# USB_MiniPower.net
KiCad netlist of a schematic drawn in EAGLE
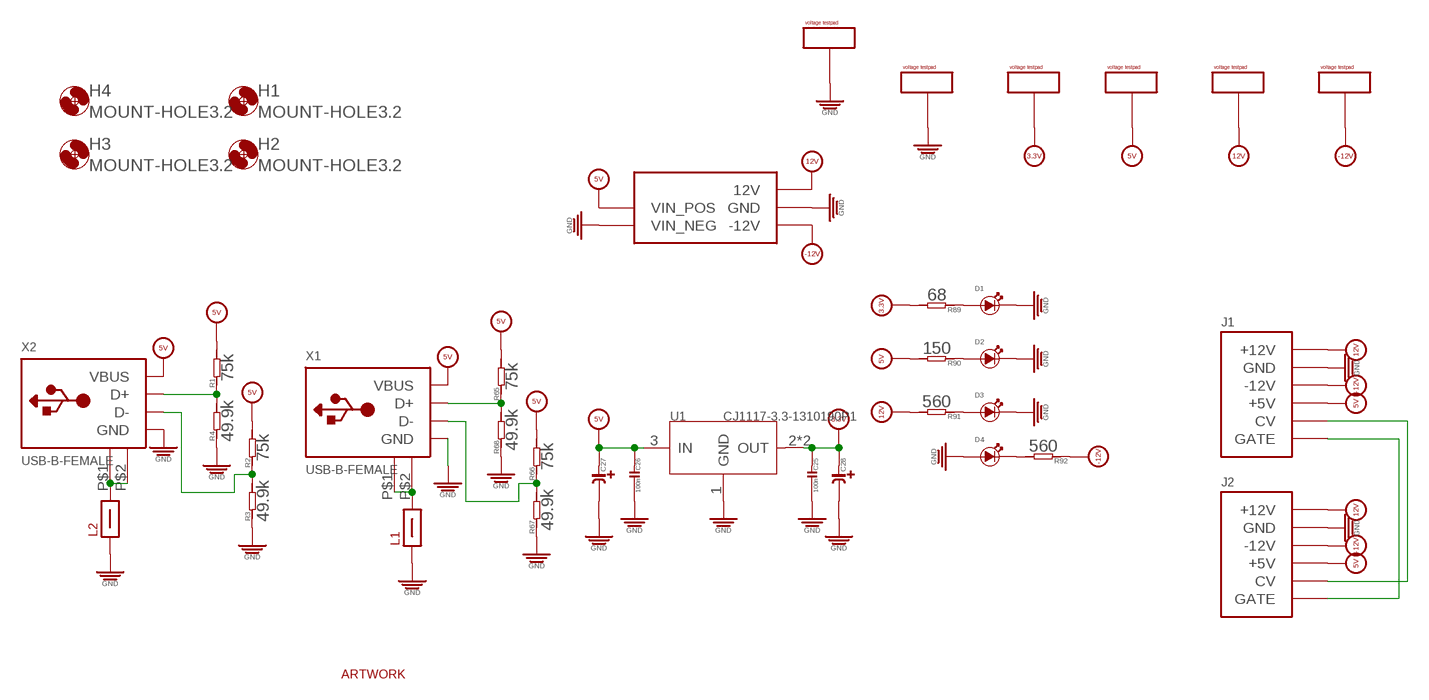
[diagram p0: schematic, sheet 1]

(export (version "E")
  (design (tool "Eeschema 10.0.6"))
  (components
    (comp (ref "C25")
      (value "100n")
      (footprint "eagle-import:C0603")
      (libsource (lib "eagle-import") (part "C-0603"))
    )
    (comp (ref "C26")
      (value "100n")
      (footprint "eagle-import:C0603")
      (libsource (lib "eagle-import") (part "C-0603"))
    )
    (comp (ref "C27")
      (value "C-POLAR-A")
      (footprint "eagle-import:CASE-A_3216")
      (libsource (lib "eagle-import") (part "C-POLAR-A"))
    )
    (comp (ref "C28")
      (value "C-POLAR-A")
      (footprint "eagle-import:CASE-A_3216")
      (libsource (lib "eagle-import") (part "C-POLAR-A"))
    )
    (comp (ref "D1")
      (value "LED")
      (footprint "eagle-import:LED0603")
      (libsource (lib "eagle-import") (part "LED"))
    )
    (comp (ref "D2")
      (value "LED")
      (footprint "eagle-import:LED0603")
      (libsource (lib "eagle-import") (part "LED"))
    )
    (comp (ref "D3")
      (value "LED")
      (footprint "eagle-import:LED0603")
      (libsource (lib "eagle-import") (part "LED"))
    )
    (comp (ref "D4")
      (value "LED")
      (footprint "eagle-import:LED0603")
      (libsource (lib "eagle-import") (part "LED"))
    )
    (comp (ref "H1")
      (value "MOUNT-HOLE3.2")
      (footprint "eagle-import:3,2")
      (libsource (lib "eagle-import") (part "MOUNT-HOLE3.2"))
    )
    (comp (ref "H2")
      (value "MOUNT-HOLE3.2")
      (footprint "eagle-import:3,2")
      (libsource (lib "eagle-import") (part "MOUNT-HOLE3.2"))
    )
    (comp (ref "H3")
      (value "MOUNT-HOLE3.2")
      (footprint "eagle-import:3,2")
      (libsource (lib "eagle-import") (part "MOUNT-HOLE3.2"))
    )
    (comp (ref "H4")
      (value "MOUNT-HOLE3.2")
      (footprint "eagle-import:3,2")
      (libsource (lib "eagle-import") (part "MOUNT-HOLE3.2"))
    )
    (comp (ref "J1")
      (value "POWER_SHROUDED_NOTEXT")
      (footprint "eagle-import:POWER_16_SHROUDED_NOTEXT")
      (libsource (lib "eagle-import") (part "POWER_SHROUDED_NOTEXT"))
    )
    (comp (ref "J2")
      (value "POWERSHROUDED")
      (footprint "eagle-import:POWER_16_SHROUDED")
      (libsource (lib "eagle-import") (part "POWERSHROUDED"))
    )
    (comp (ref "L1")
      (value "FERRITE_1812")
      (footprint "eagle-import:FERRITE_1812")
      (libsource (lib "eagle-import") (part "FERRITE_1812"))
    )
    (comp (ref "L2")
      (value "FERRITE_1812")
      (footprint "eagle-import:FERRITE_1812")
      (libsource (lib "eagle-import") (part "FERRITE_1812"))
    )
    (comp (ref "R1")
      (value "75k")
      (footprint "eagle-import:R0603")
      (libsource (lib "eagle-import") (part "R-0603"))
    )
    (comp (ref "R2")
      (value "75k")
      (footprint "eagle-import:R0603")
      (libsource (lib "eagle-import") (part "R-0603"))
    )
    (comp (ref "R3")
      (value "49.9k")
      (footprint "eagle-import:R0603")
      (libsource (lib "eagle-import") (part "R-0603"))
    )
    (comp (ref "R4")
      (value "49.9k")
      (footprint "eagle-import:R0603")
      (libsource (lib "eagle-import") (part "R-0603"))
    )
    (comp (ref "R65")
      (value "75k")
      (footprint "eagle-import:R0603")
      (libsource (lib "eagle-import") (part "R-0603"))
    )
    (comp (ref "R66")
      (value "75k")
      (footprint "eagle-import:R0603")
      (libsource (lib "eagle-import") (part "R-0603"))
    )
    (comp (ref "R67")
      (value "49.9k")
      (footprint "eagle-import:R0603")
      (libsource (lib "eagle-import") (part "R-0603"))
    )
    (comp (ref "R68")
      (value "49.9k")
      (footprint "eagle-import:R0603")
      (libsource (lib "eagle-import") (part "R-0603"))
    )
    (comp (ref "R89")
      (value "68")
      (footprint "eagle-import:R0603")
      (libsource (lib "eagle-import") (part "R-0603"))
    )
    (comp (ref "R90")
      (value "150")
      (footprint "eagle-import:R0603")
      (libsource (lib "eagle-import") (part "R-0603"))
    )
    (comp (ref "R91")
      (value "560")
      (footprint "eagle-import:R0603")
      (libsource (lib "eagle-import") (part "R-0603"))
    )
    (comp (ref "R92")
      (value "560")
      (footprint "eagle-import:R0603")
      (libsource (lib "eagle-import") (part "R-0603"))
    )
    (comp (ref "U$7")
      (value "VOLTAGETESTPAD_BIG")
      (footprint "eagle-import:POWERTESTPAD_BIG")
      (fields (field (name "DESC") "3.3V"))
      (libsource (lib "eagle-import") (part "VOLTAGETESTPAD_BIG"))
    )
    (comp (ref "U$8")
      (value "VOLTAGETESTPAD_BIG")
      (footprint "eagle-import:POWERTESTPAD_BIG")
      (fields (field (name "DESC") "5V"))
      (libsource (lib "eagle-import") (part "VOLTAGETESTPAD_BIG"))
    )
    (comp (ref "U$9")
      (value "VOLTAGETESTPAD_BIG")
      (footprint "eagle-import:POWERTESTPAD_BIG")
      (fields (field (name "DESC") "12V"))
      (libsource (lib "eagle-import") (part "VOLTAGETESTPAD_BIG"))
    )
    (comp (ref "U$10")
      (value "VOLTAGETESTPAD_BIG")
      (footprint "eagle-import:POWERTESTPAD_BIG")
      (fields (field (name "DESC") "-12V"))
      (libsource (lib "eagle-import") (part "VOLTAGETESTPAD_BIG"))
    )
    (comp (ref "U$11")
      (value "VOLTAGETESTPAD_BIG")
      (footprint "eagle-import:POWERTESTPAD_BIG")
      (fields (field (name "DESC") "GND"))
      (libsource (lib "eagle-import") (part "VOLTAGETESTPAD_BIG"))
    )
    (comp (ref "U$16")
      (value "VOLTAGETESTPAD_BIG")
      (footprint "eagle-import:POWERTESTPAD_BIG")
      (fields (field (name "DESC") "GND"))
      (libsource (lib "eagle-import") (part "VOLTAGETESTPAD_BIG"))
    )
    (comp (ref "U$17")
      (value "TINRS_ARTWORKTINYDATE")
      (footprint "eagle-import:JUSTATINYROCKET_DATECODE")
      (libsource (lib "eagle-import") (part "TINRS_ARTWORKTINYDATE"))
    )
    (comp (ref "U$42")
      (value "CINCONBRICK_12V")
      (footprint "eagle-import:CINCONBRICK")
      (libsource (lib "eagle-import") (part "CINCONBRICK_12V"))
    )
    (comp (ref "U1")
      (value "CJ1117-3.3-1310190P1")
      (footprint "eagle-import:SOT223")
      (libsource (lib "eagle-import") (part "CJ1117-3.3-1310190P1"))
    )
    (comp (ref "X1")
      (value "USB-B-FEMALE")
      (footprint "eagle-import:FCI61729")
      (libsource (lib "eagle-import") (part "USB-B-FEMALE"))
    )
    (comp (ref "X2")
      (value "USB-B-FEMALE")
      (footprint "eagle-import:FCI61729")
      (libsource (lib "eagle-import") (part "USB-B-FEMALE"))
    )
  )
  (nets
    (net (code "1") (name "-12V") (class "Default")
      (node (ref "J1") (pin "1") (pinfunction "-12V_1") (pintype "bidirectional"))
      (node (ref "J1") (pin "2") (pinfunction "-12V_2") (pintype "bidirectional"))
      (node (ref "J2") (pin "1") (pinfunction "-12V_1") (pintype "bidirectional"))
      (node (ref "J2") (pin "2") (pinfunction "-12V_2") (pintype "bidirectional"))
      (node (ref "R92") (pin "1") (pinfunction "1_1") (pintype "bidirectional"))
      (node (ref "U$10") (pin "P$1") (pinfunction "VOLTAGE_P$1") (pintype "bidirectional"))
      (node (ref "U$10") (pin "P$2") (pinfunction "VOLTAGE_P$2") (pintype "bidirectional"))
      (node (ref "U$10") (pin "P$3") (pinfunction "VOLTAGE_P$3") (pintype "bidirectional"))
      (node (ref "U$42") (pin "2") (pinfunction "-12V_2") (pintype "power_in"))
      (node (ref "U$42") (pin "23") (pinfunction "-12V_23") (pintype "power_in"))
    )
    (net (code "2") (name "3.3V") (class "Default")
      (node (ref "C25") (pin "1") (pinfunction "1_1") (pintype "bidirectional"))
      (node (ref "C28") (pin "+") (pinfunction "1_+") (pintype "bidirectional"))
      (node (ref "R89") (pin "2") (pinfunction "2_2") (pintype "bidirectional"))
      (node (ref "U$7") (pin "P$1") (pinfunction "VOLTAGE_P$1") (pintype "bidirectional"))
      (node (ref "U$7") (pin "P$2") (pinfunction "VOLTAGE_P$2") (pintype "bidirectional"))
      (node (ref "U$7") (pin "P$3") (pinfunction "VOLTAGE_P$3") (pintype "bidirectional"))
      (node (ref "U1") (pin "2") (pinfunction "OUT_2") (pintype "bidirectional"))
      (node (ref "U1") (pin "TER") (pinfunction "OUT_TER") (pintype "bidirectional"))
    )
    (net (code "3") (name "5V") (class "Default")
      (node (ref "C26") (pin "1") (pinfunction "1_1") (pintype "bidirectional"))
      (node (ref "C27") (pin "+") (pinfunction "1_+") (pintype "bidirectional"))
      (node (ref "J1") (pin "11") (pinfunction "+5V_11") (pintype "bidirectional"))
      (node (ref "J1") (pin "12") (pinfunction "+5V_12") (pintype "bidirectional"))
      (node (ref "J2") (pin "11") (pinfunction "+5V_11") (pintype "bidirectional"))
      (node (ref "J2") (pin "12") (pinfunction "+5V_12") (pintype "bidirectional"))
      (node (ref "R1") (pin "2") (pinfunction "2_2") (pintype "bidirectional"))
      (node (ref "R2") (pin "2") (pinfunction "2_2") (pintype "bidirectional"))
      (node (ref "R65") (pin "2") (pinfunction "2_2") (pintype "bidirectional"))
      (node (ref "R66") (pin "2") (pinfunction "2_2") (pintype "bidirectional"))
      (node (ref "R90") (pin "2") (pinfunction "2_2") (pintype "bidirectional"))
      (node (ref "U$42") (pin "1") (pinfunction "VIN_POS_1") (pintype "bidirectional"))
      (node (ref "U$42") (pin "24") (pinfunction "VIN_POS_24") (pintype "bidirectional"))
      (node (ref "U$8") (pin "P$1") (pinfunction "VOLTAGE_P$1") (pintype "bidirectional"))
      (node (ref "U$8") (pin "P$2") (pinfunction "VOLTAGE_P$2") (pintype "bidirectional"))
      (node (ref "U$8") (pin "P$3") (pinfunction "VOLTAGE_P$3") (pintype "bidirectional"))
      (node (ref "U1") (pin "3") (pinfunction "IN_3") (pintype "bidirectional"))
      (node (ref "X1") (pin "1") (pinfunction "VBUS_1") (pintype "power_in"))
      (node (ref "X2") (pin "1") (pinfunction "VBUS_1") (pintype "power_in"))
    )
    (net (code "4") (name "12V") (class "Default")
      (node (ref "J1") (pin "10") (pinfunction "+12V_10") (pintype "bidirectional"))
      (node (ref "J1") (pin "9") (pinfunction "+12V_9") (pintype "bidirectional"))
      (node (ref "J2") (pin "10") (pinfunction "+12V_10") (pintype "bidirectional"))
      (node (ref "J2") (pin "9") (pinfunction "+12V_9") (pintype "bidirectional"))
      (node (ref "R91") (pin "2") (pinfunction "2_2") (pintype "bidirectional"))
      (node (ref "U$42") (pin "11") (pinfunction "12V_11") (pintype "power_in"))
      (node (ref "U$42") (pin "14") (pinfunction "12V_14") (pintype "power_in"))
      (node (ref "U$9") (pin "P$1") (pinfunction "VOLTAGE_P$1") (pintype "bidirectional"))
      (node (ref "U$9") (pin "P$2") (pinfunction "VOLTAGE_P$2") (pintype "bidirectional"))
      (node (ref "U$9") (pin "P$3") (pinfunction "VOLTAGE_P$3") (pintype "bidirectional"))
    )
    (net (code "5") (name "GND") (class "Default")
      (node (ref "C25") (pin "2") (pinfunction "2_2") (pintype "bidirectional"))
      (node (ref "C26") (pin "2") (pinfunction "2_2") (pintype "bidirectional"))
      (node (ref "C27") (pin "-") (pinfunction "2_-") (pintype "bidirectional"))
      (node (ref "C28") (pin "-") (pinfunction "2_-") (pintype "bidirectional"))
      (node (ref "D1") (pin "-") (pinfunction "-_-") (pintype "passive"))
      (node (ref "D2") (pin "-") (pinfunction "-_-") (pintype "passive"))
      (node (ref "D3") (pin "-") (pinfunction "-_-") (pintype "passive"))
      (node (ref "D4") (pin "+") (pinfunction "+_+") (pintype "passive"))
      (node (ref "J1") (pin "3") (pinfunction "GND_3") (pintype "bidirectional"))
      (node (ref "J1") (pin "4") (pinfunction "GND_4") (pintype "bidirectional"))
      (node (ref "J1") (pin "5") (pinfunction "GND_5") (pintype "bidirectional"))
      (node (ref "J1") (pin "6") (pinfunction "GND_6") (pintype "bidirectional"))
      (node (ref "J1") (pin "7") (pinfunction "GND_7") (pintype "bidirectional"))
      (node (ref "J1") (pin "8") (pinfunction "GND_8") (pintype "bidirectional"))
      (node (ref "J2") (pin "3") (pinfunction "GND_3") (pintype "bidirectional"))
      (node (ref "J2") (pin "4") (pinfunction "GND_4") (pintype "bidirectional"))
      (node (ref "J2") (pin "5") (pinfunction "GND_5") (pintype "bidirectional"))
      (node (ref "J2") (pin "6") (pinfunction "GND_6") (pintype "bidirectional"))
      (node (ref "J2") (pin "7") (pinfunction "GND_7") (pintype "bidirectional"))
      (node (ref "J2") (pin "8") (pinfunction "GND_8") (pintype "bidirectional"))
      (node (ref "L1") (pin "P$1") (pinfunction "P$1_P$1") (pintype "bidirectional"))
      (node (ref "L2") (pin "P$1") (pinfunction "P$1_P$1") (pintype "bidirectional"))
      (node (ref "R3") (pin "1") (pinfunction "1_1") (pintype "bidirectional"))
      (node (ref "R4") (pin "1") (pinfunction "1_1") (pintype "bidirectional"))
      (node (ref "R67") (pin "1") (pinfunction "1_1") (pintype "bidirectional"))
      (node (ref "R68") (pin "1") (pinfunction "1_1") (pintype "bidirectional"))
      (node (ref "U$11") (pin "P$1") (pinfunction "VOLTAGE_P$1") (pintype "bidirectional"))
      (node (ref "U$11") (pin "P$2") (pinfunction "VOLTAGE_P$2") (pintype "bidirectional"))
      (node (ref "U$11") (pin "P$3") (pinfunction "VOLTAGE_P$3") (pintype "bidirectional"))
      (node (ref "U$16") (pin "P$1") (pinfunction "VOLTAGE_P$1") (pintype "bidirectional"))
      (node (ref "U$16") (pin "P$2") (pinfunction "VOLTAGE_P$2") (pintype "bidirectional"))
      (node (ref "U$16") (pin "P$3") (pinfunction "VOLTAGE_P$3") (pintype "bidirectional"))
      (node (ref "U$42") (pin "10") (pinfunction "GND_10") (pintype "bidirectional"))
      (node (ref "U$42") (pin "12") (pinfunction "VIN_NEG_12") (pintype "bidirectional"))
      (node (ref "U$42") (pin "13") (pinfunction "VIN_NEG_13") (pintype "bidirectional"))
      (node (ref "U$42") (pin "15") (pinfunction "GND_15") (pintype "bidirectional"))
      (node (ref "U$42") (pin "22") (pinfunction "GND_22") (pintype "bidirectional"))
      (node (ref "U$42") (pin "3") (pinfunction "GND_3") (pintype "bidirectional"))
      (node (ref "U1") (pin "1") (pinfunction "GND_1") (pintype "bidirectional"))
      (node (ref "X1") (pin "4") (pinfunction "GND_4") (pintype "power_in"))
      (node (ref "X2") (pin "4") (pinfunction "GND_4") (pintype "power_in"))
    )
    (net (code "6") (name "Net-(D1-Pad+)") (class "Default")
      (node (ref "D1") (pin "+") (pinfunction "+_+") (pintype "passive"))
      (node (ref "R89") (pin "1") (pinfunction "1_1") (pintype "bidirectional"))
    )
    (net (code "7") (name "Net-(D2-Pad+)") (class "Default")
      (node (ref "D2") (pin "+") (pinfunction "+_+") (pintype "passive"))
      (node (ref "R90") (pin "1") (pinfunction "1_1") (pintype "bidirectional"))
    )
    (net (code "8") (name "Net-(D3-Pad+)") (class "Default")
      (node (ref "D3") (pin "+") (pinfunction "+_+") (pintype "passive"))
      (node (ref "R91") (pin "1") (pinfunction "1_1") (pintype "bidirectional"))
    )
    (net (code "9") (name "Net-(D4-Pad-)") (class "Default")
      (node (ref "D4") (pin "-") (pinfunction "-_-") (pintype "passive"))
      (node (ref "R92") (pin "2") (pinfunction "2_2") (pintype "bidirectional"))
    )
    (net (code "10") (name "Net-(J1-CV-Pad13)") (class "Default")
      (node (ref "J1") (pin "13") (pinfunction "CV_13") (pintype "bidirectional"))
      (node (ref "J1") (pin "14") (pinfunction "CV_14") (pintype "bidirectional"))
      (node (ref "J2") (pin "13") (pinfunction "CV_13") (pintype "bidirectional"))
      (node (ref "J2") (pin "14") (pinfunction "CV_14") (pintype "bidirectional"))
    )
    (net (code "11") (name "Net-(J1-GATE-Pad15)") (class "Default")
      (node (ref "J1") (pin "15") (pinfunction "GATE_15") (pintype "bidirectional"))
      (node (ref "J1") (pin "16") (pinfunction "GATE_16") (pintype "bidirectional"))
      (node (ref "J2") (pin "15") (pinfunction "GATE_15") (pintype "bidirectional"))
      (node (ref "J2") (pin "16") (pinfunction "GATE_16") (pintype "bidirectional"))
    )
    (net (code "12") (name "Net-(X1-D+)") (class "Default")
      (node (ref "R65") (pin "1") (pinfunction "1_1") (pintype "bidirectional"))
      (node (ref "R68") (pin "2") (pinfunction "2_2") (pintype "bidirectional"))
      (node (ref "X1") (pin "3") (pinfunction "D+_3") (pintype "bidirectional"))
    )
    (net (code "13") (name "Net-(X1-D-)") (class "Default")
      (node (ref "R66") (pin "1") (pinfunction "1_1") (pintype "bidirectional"))
      (node (ref "R67") (pin "2") (pinfunction "2_2") (pintype "bidirectional"))
      (node (ref "X1") (pin "2") (pinfunction "D-_2") (pintype "bidirectional"))
    )
    (net (code "14") (name "Net-(X1-GND1)") (class "Default")
      (node (ref "L1") (pin "P$2") (pinfunction "P$2_P$2") (pintype "bidirectional"))
      (node (ref "X1") (pin "P$1") (pinfunction "GND1_P$1") (pintype "power_in"))
      (node (ref "X1") (pin "P$2") (pinfunction "GND2_P$2") (pintype "power_in"))
    )
    (net (code "15") (name "Net-(X2-D+)") (class "Default")
      (node (ref "R1") (pin "1") (pinfunction "1_1") (pintype "bidirectional"))
      (node (ref "R4") (pin "2") (pinfunction "2_2") (pintype "bidirectional"))
      (node (ref "X2") (pin "3") (pinfunction "D+_3") (pintype "bidirectional"))
    )
    (net (code "16") (name "Net-(X2-D-)") (class "Default")
      (node (ref "R2") (pin "1") (pinfunction "1_1") (pintype "bidirectional"))
      (node (ref "R3") (pin "2") (pinfunction "2_2") (pintype "bidirectional"))
      (node (ref "X2") (pin "2") (pinfunction "D-_2") (pintype "bidirectional"))
    )
    (net (code "17") (name "Net-(X2-GND1)") (class "Default")
      (node (ref "L2") (pin "P$2") (pinfunction "P$2_P$2") (pintype "bidirectional"))
      (node (ref "X2") (pin "P$1") (pinfunction "GND1_P$1") (pintype "power_in"))
      (node (ref "X2") (pin "P$2") (pinfunction "GND2_P$2") (pintype "power_in"))
    )
  )
)
